# LED_Buttons.net
KiCad netlist of a schematic drawn in Altium Designer
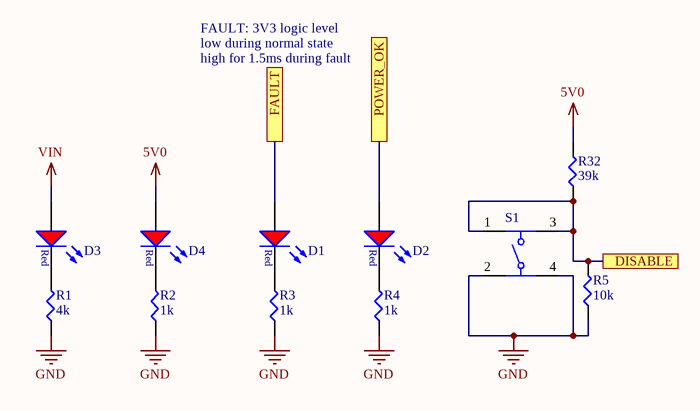
[diagram p0: LED_Buttons.SchDoc]

(export (version "E")
  (design (tool "Eeschema 10.0.6"))
  (components
    (comp (ref "D1")
      (value "150060RS75000")
      (footprint "WL-SMCW_0603")
      (description "WL-SMCW SMD Mono-color Chip LED Waterclear, size 0603, Red, 2 V, 140°")
      (fields (field (name "MF") "Wuerth Elektronik") (field (name "CREATED") "2018_09_06_AGeiger"))
      (libsource (lib "UltraZohm_ADC") (part "LED_Red_0603"))
    )
    (comp (ref "D2")
      (value "150060RS75000")
      (footprint "WL-SMCW_0603")
      (description "WL-SMCW SMD Mono-color Chip LED Waterclear, size 0603, Red, 2 V, 140°")
      (fields (field (name "MF") "Wuerth Elektronik") (field (name "CREATED") "2018_09_06_AGeiger"))
      (libsource (lib "UltraZohm_ADC") (part "LED_Red_0603"))
    )
    (comp (ref "D3")
      (value "150060RS75000")
      (footprint "WL-SMCW_0603")
      (description "WL-SMCW SMD Mono-color Chip LED Waterclear, size 0603, Red, 2 V, 140°")
      (fields (field (name "MF") "Wuerth Elektronik") (field (name "CREATED") "2018_09_06_AGeiger"))
      (libsource (lib "UltraZohm_ADC") (part "LED_Red_0603"))
    )
    (comp (ref "D4")
      (value "150060RS75000")
      (footprint "WL-SMCW_0603")
      (description "WL-SMCW SMD Mono-color Chip LED Waterclear, size 0603, Red, 2 V, 140°")
      (fields (field (name "MF") "Wuerth Elektronik") (field (name "CREATED") "2018_09_06_AGeiger"))
      (libsource (lib "UltraZohm_ADC") (part "LED_Red_0603"))
    )
    (comp (ref "R1")
      (value "4k")
      (footprint "RESC0603")
      (description "RES SMD")
      (fields (field (name "PART NUMBER") "Generic 1% tol.") (field (name "PUBLISHER") "Generic"))
      (libsource (lib "Res_SMD") (part "RES_SMD"))
    )
    (comp (ref "R2")
      (value "1k")
      (footprint "RESC0603")
      (description "RES SMD")
      (fields (field (name "PART NUMBER") "Generic 1% tol.") (field (name "PUBLISHER") "Generic"))
      (libsource (lib "Res_SMD") (part "RES_SMD"))
    )
    (comp (ref "R3")
      (value "1k")
      (footprint "RESC0603")
      (description "RES SMD")
      (fields (field (name "PART NUMBER") "Generic 1% tol.") (field (name "PUBLISHER") "Generic"))
      (libsource (lib "Res_SMD") (part "RES_SMD"))
    )
    (comp (ref "R4")
      (value "1k")
      (footprint "RESC0603")
      (description "RES SMD")
      (fields (field (name "PART NUMBER") "Generic 1% tol.") (field (name "PUBLISHER") "Generic"))
      (libsource (lib "Res_SMD") (part "RES_SMD"))
    )
    (comp (ref "R5")
      (value "10k")
      (footprint "RESC0603")
      (description "RES SMD")
      (fields (field (name "PART NUMBER") "Generic 1% tol.") (field (name "PUBLISHER") "Generic"))
      (libsource (lib "Res_SMD") (part "RES_SMD"))
    )
    (comp (ref "R32")
      (value "39k")
      (footprint "RESC0603")
      (description "RES SMD")
      (fields (field (name "PART NUMBER") "Generic 1% tol.") (field (name "PUBLISHER") "Generic"))
      (libsource (lib "Res_SMD") (part "RES_SMD"))
    )
    (comp (ref "S1")
      (value "434153017835")
      (footprint "434153017835")
      (description "WS-TASV J-Bend SMT Tact Switch 3.5x2.9mm, height 1.7mm, 350gf")
      (fields (field (name "PUBLISHER") "Wurth Elektronik"))
      (libsource (lib "WE_WS-TASV_rev19b") (part "434153017835"))
    )
  )
  (nets
    (net (code "1") (name "/DISABLE") (class "Default")
      (node (ref "R32") (pin "1") (pinfunction "1_1") (pintype "passive"))
      (node (ref "R5") (pin "2") (pinfunction "2_2") (pintype "passive"))
      (node (ref "S1") (pin "1") (pinfunction "1_1") (pintype "passive"))
      (node (ref "S1") (pin "3") (pinfunction "3_3") (pintype "passive"))
    )
    (net (code "2") (name "/FAULT") (class "Default")
      (node (ref "D1") (pin "2") (pinfunction "A_2") (pintype "passive"))
    )
    (net (code "3") (name "/POWER_OK") (class "Default")
      (node (ref "D2") (pin "2") (pinfunction "A_2") (pintype "passive"))
    )
    (net (code "4") (name "5V0") (class "Default")
      (node (ref "D4") (pin "2") (pinfunction "A_2") (pintype "passive"))
      (node (ref "R32") (pin "2") (pinfunction "2_2") (pintype "passive"))
    )
    (net (code "5") (name "GND") (class "Default")
      (node (ref "R1") (pin "1") (pinfunction "1_1") (pintype "passive"))
      (node (ref "R2") (pin "1") (pinfunction "1_1") (pintype "passive"))
      (node (ref "R3") (pin "1") (pinfunction "1_1") (pintype "passive"))
      (node (ref "R4") (pin "1") (pinfunction "1_1") (pintype "passive"))
      (node (ref "R5") (pin "1") (pinfunction "1_1") (pintype "passive"))
      (node (ref "S1") (pin "2") (pinfunction "2_2") (pintype "passive"))
      (node (ref "S1") (pin "4") (pinfunction "4_4") (pintype "passive"))
    )
    (net (code "6") (name "Net-(D1-K)") (class "Default")
      (node (ref "D1") (pin "1") (pinfunction "K_1") (pintype "passive"))
      (node (ref "R3") (pin "2") (pinfunction "2_2") (pintype "passive"))
    )
    (net (code "7") (name "Net-(D2-K)") (class "Default")
      (node (ref "D2") (pin "1") (pinfunction "K_1") (pintype "passive"))
      (node (ref "R4") (pin "2") (pinfunction "2_2") (pintype "passive"))
    )
    (net (code "8") (name "Net-(D3-K)") (class "Default")
      (node (ref "D3") (pin "1") (pinfunction "K_1") (pintype "passive"))
      (node (ref "R1") (pin "2") (pinfunction "2_2") (pintype "passive"))
    )
    (net (code "9") (name "Net-(D4-K)") (class "Default")
      (node (ref "D4") (pin "1") (pinfunction "K_1") (pintype "passive"))
      (node (ref "R2") (pin "2") (pinfunction "2_2") (pintype "passive"))
    )
    (net (code "10") (name "VIN") (class "Default")
      (node (ref "D3") (pin "2") (pinfunction "A_2") (pintype "passive"))
    )
  )
)
